# 12vAC_light.net
KiCad netlist of a schematic drawn in EAGLE
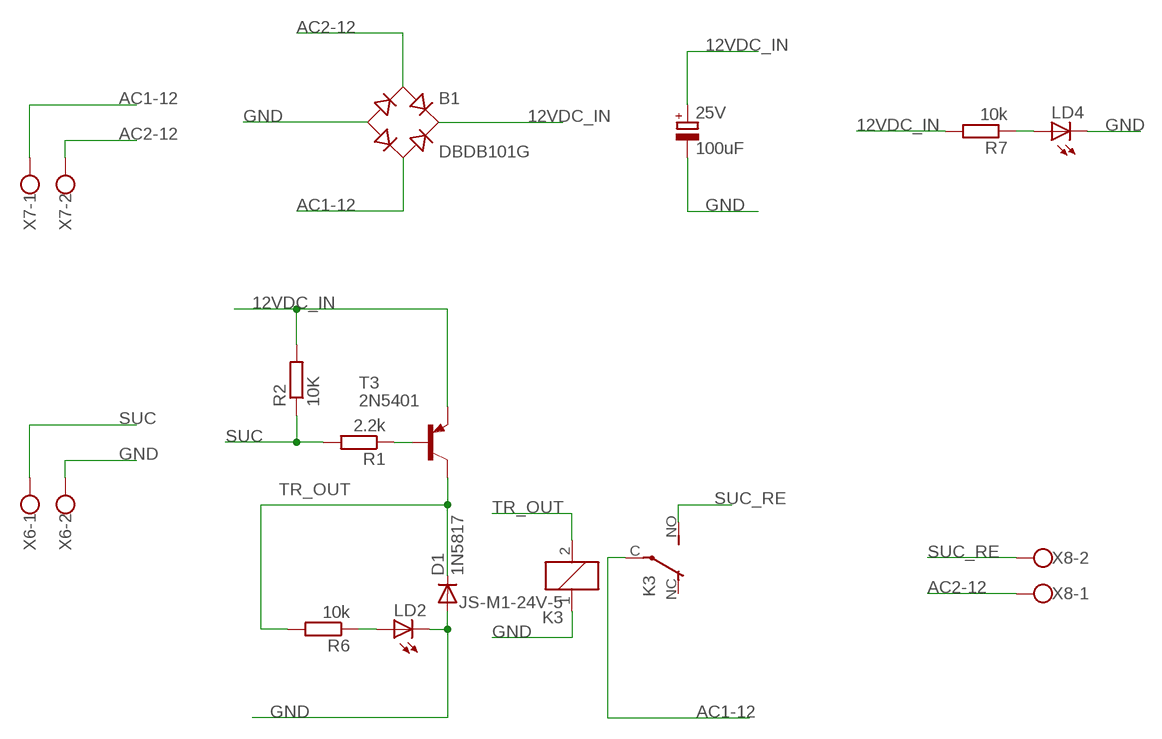
[diagram p0: schematic, sheet 1]

(export (version "E")
  (design (tool "Eeschema 10.0.6"))
  (components
    (comp (ref "25V")
      (value "100uF")
      (footprint "eagle-import:E3,5-8")
      (libsource (lib "eagle-import") (part "CPOL-EUE3.5-8"))
    )
    (comp (ref "B1")
      (value "DBDB101G")
      (footprint "eagle-import:DB")
      (libsource (lib "eagle-import") (part "DB?GDB101"))
    )
    (comp (ref "D1")
      (value "1N5817")
      (footprint "eagle-import:DO41-10")
      (libsource (lib "eagle-import") (part "1N4004"))
    )
    (comp (ref "K3")
      (value "JS-M1-24V-5")
      (footprint "eagle-import:JS-M")
      (fields (field (name "MF") "FARNELL") (field (name "MPN") "JSM1-12V-5"))
      (libsource (lib "eagle-import") (part "JS-M1-12V-5"))
    )
    (comp (ref "LD2")
      (value "LED5MM")
      (footprint "eagle-import:LED5MM")
      (libsource (lib "eagle-import") (part "LED5MM"))
    )
    (comp (ref "LD4")
      (value "LED5MM")
      (footprint "eagle-import:LED5MM")
      (libsource (lib "eagle-import") (part "LED5MM"))
    )
    (comp (ref "R1")
      (value "2.2k")
      (footprint "eagle-import:0207_10")
      (libsource (lib "eagle-import") (part "R-EU_0207/10"))
    )
    (comp (ref "R2")
      (value "10K")
      (footprint "eagle-import:0207_10")
      (libsource (lib "eagle-import") (part "R-EU_0207/10"))
    )
    (comp (ref "R6")
      (value "10k")
      (footprint "eagle-import:0207_10")
      (libsource (lib "eagle-import") (part "R-EU_0207/10"))
    )
    (comp (ref "R7")
      (value "10k")
      (footprint "eagle-import:0207_10")
      (libsource (lib "eagle-import") (part "R-EU_0207/10"))
    )
    (comp (ref "T3")
      (value "2N5401")
      (footprint "eagle-import:TO92-EBC")
      (libsource (lib "eagle-import") (part "-PNP-TO92-EBC2N5401"))
    )
    (comp (ref "X6")
      (value "W237-102")
      (footprint "eagle-import:W237-102")
      (libsource (lib "eagle-import") (part "W237-102"))
    )
    (comp (ref "X7")
      (value "W237-102")
      (footprint "eagle-import:W237-102")
      (libsource (lib "eagle-import") (part "W237-102"))
    )
    (comp (ref "X8")
      (value "W237-102")
      (footprint "eagle-import:W237-102")
      (libsource (lib "eagle-import") (part "W237-102"))
    )
  )
  (nets
    (net (code "1") (name "/12VDC_IN") (class "Default")
      (node (ref "25V") (pin "+") (pinfunction "+_+") (pintype "passive"))
      (node (ref "B1") (pin "+") (pinfunction "+_+") (pintype "passive"))
      (node (ref "R2") (pin "2") (pinfunction "2_2") (pintype "passive"))
      (node (ref "R7") (pin "2") (pinfunction "2_2") (pintype "passive"))
      (node (ref "T3") (pin "E") (pinfunction "E_E") (pintype "passive"))
    )
    (net (code "2") (name "/AC1-12") (class "Default")
      (node (ref "B1") (pin "AC2") (pinfunction "AC2_AC2") (pintype "passive"))
      (node (ref "K3") (pin "C") (pinfunction "P_C") (pintype "passive"))
      (node (ref "X7") (pin "1") (pinfunction "KL_1") (pintype "passive"))
    )
    (net (code "3") (name "/AC2-12") (class "Default")
      (node (ref "B1") (pin "AC1") (pinfunction "AC1_AC1") (pintype "passive"))
      (node (ref "X7") (pin "2") (pinfunction "KL_2") (pintype "passive"))
      (node (ref "X8") (pin "1") (pinfunction "KL_1") (pintype "passive"))
    )
    (net (code "4") (name "/GND") (class "Default")
      (node (ref "25V") (pin "-") (pinfunction "-_-") (pintype "passive"))
      (node (ref "B1") (pin "-") (pinfunction "-_-") (pintype "passive"))
      (node (ref "D1") (pin "A") (pinfunction "A_A") (pintype "passive"))
      (node (ref "K3") (pin "1") (pinfunction "1_1") (pintype "passive"))
      (node (ref "LD2") (pin "K") (pinfunction "C_K") (pintype "passive"))
      (node (ref "LD4") (pin "K") (pinfunction "C_K") (pintype "passive"))
      (node (ref "X6") (pin "2") (pinfunction "KL_2") (pintype "passive"))
    )
    (net (code "5") (name "/SUC") (class "Default")
      (node (ref "R1") (pin "2") (pinfunction "2_2") (pintype "passive"))
      (node (ref "R2") (pin "1") (pinfunction "1_1") (pintype "passive"))
      (node (ref "X6") (pin "1") (pinfunction "KL_1") (pintype "passive"))
    )
    (net (code "6") (name "/SUC_RE") (class "Default")
      (node (ref "K3") (pin "NO") (pinfunction "S_NO") (pintype "passive"))
      (node (ref "X8") (pin "2") (pinfunction "KL_2") (pintype "passive"))
    )
    (net (code "7") (name "/TR_OUT") (class "Default")
      (node (ref "D1") (pin "C") (pinfunction "C_C") (pintype "passive"))
      (node (ref "K3") (pin "2") (pinfunction "2_2") (pintype "passive"))
      (node (ref "R6") (pin "2") (pinfunction "2_2") (pintype "passive"))
      (node (ref "T3") (pin "C") (pinfunction "C_C") (pintype "passive"))
    )
    (net (code "8") (name "Net-(LD2-PadA)") (class "Default")
      (node (ref "LD2") (pin "A") (pinfunction "A_A") (pintype "passive"))
      (node (ref "R6") (pin "1") (pinfunction "1_1") (pintype "passive"))
    )
    (net (code "9") (name "Net-(LD4-PadA)") (class "Default")
      (node (ref "LD4") (pin "A") (pinfunction "A_A") (pintype "passive"))
      (node (ref "R7") (pin "1") (pinfunction "1_1") (pintype "passive"))
    )
    (net (code "10") (name "Net-(R1-Pad1)") (class "Default")
      (node (ref "R1") (pin "1") (pinfunction "1_1") (pintype "passive"))
      (node (ref "T3") (pin "B") (pinfunction "B_B") (pintype "passive"))
    )
    (net (code "11") (name "unconnected-(K3B-O-PadNC)") (class "Default")
      (node (ref "K3") (pin "NC") (pinfunction "O_NC") (pintype "passive"))
    )
  )
)
